# SCH.net
KiCad netlist of a schematic drawn in Altium Designer
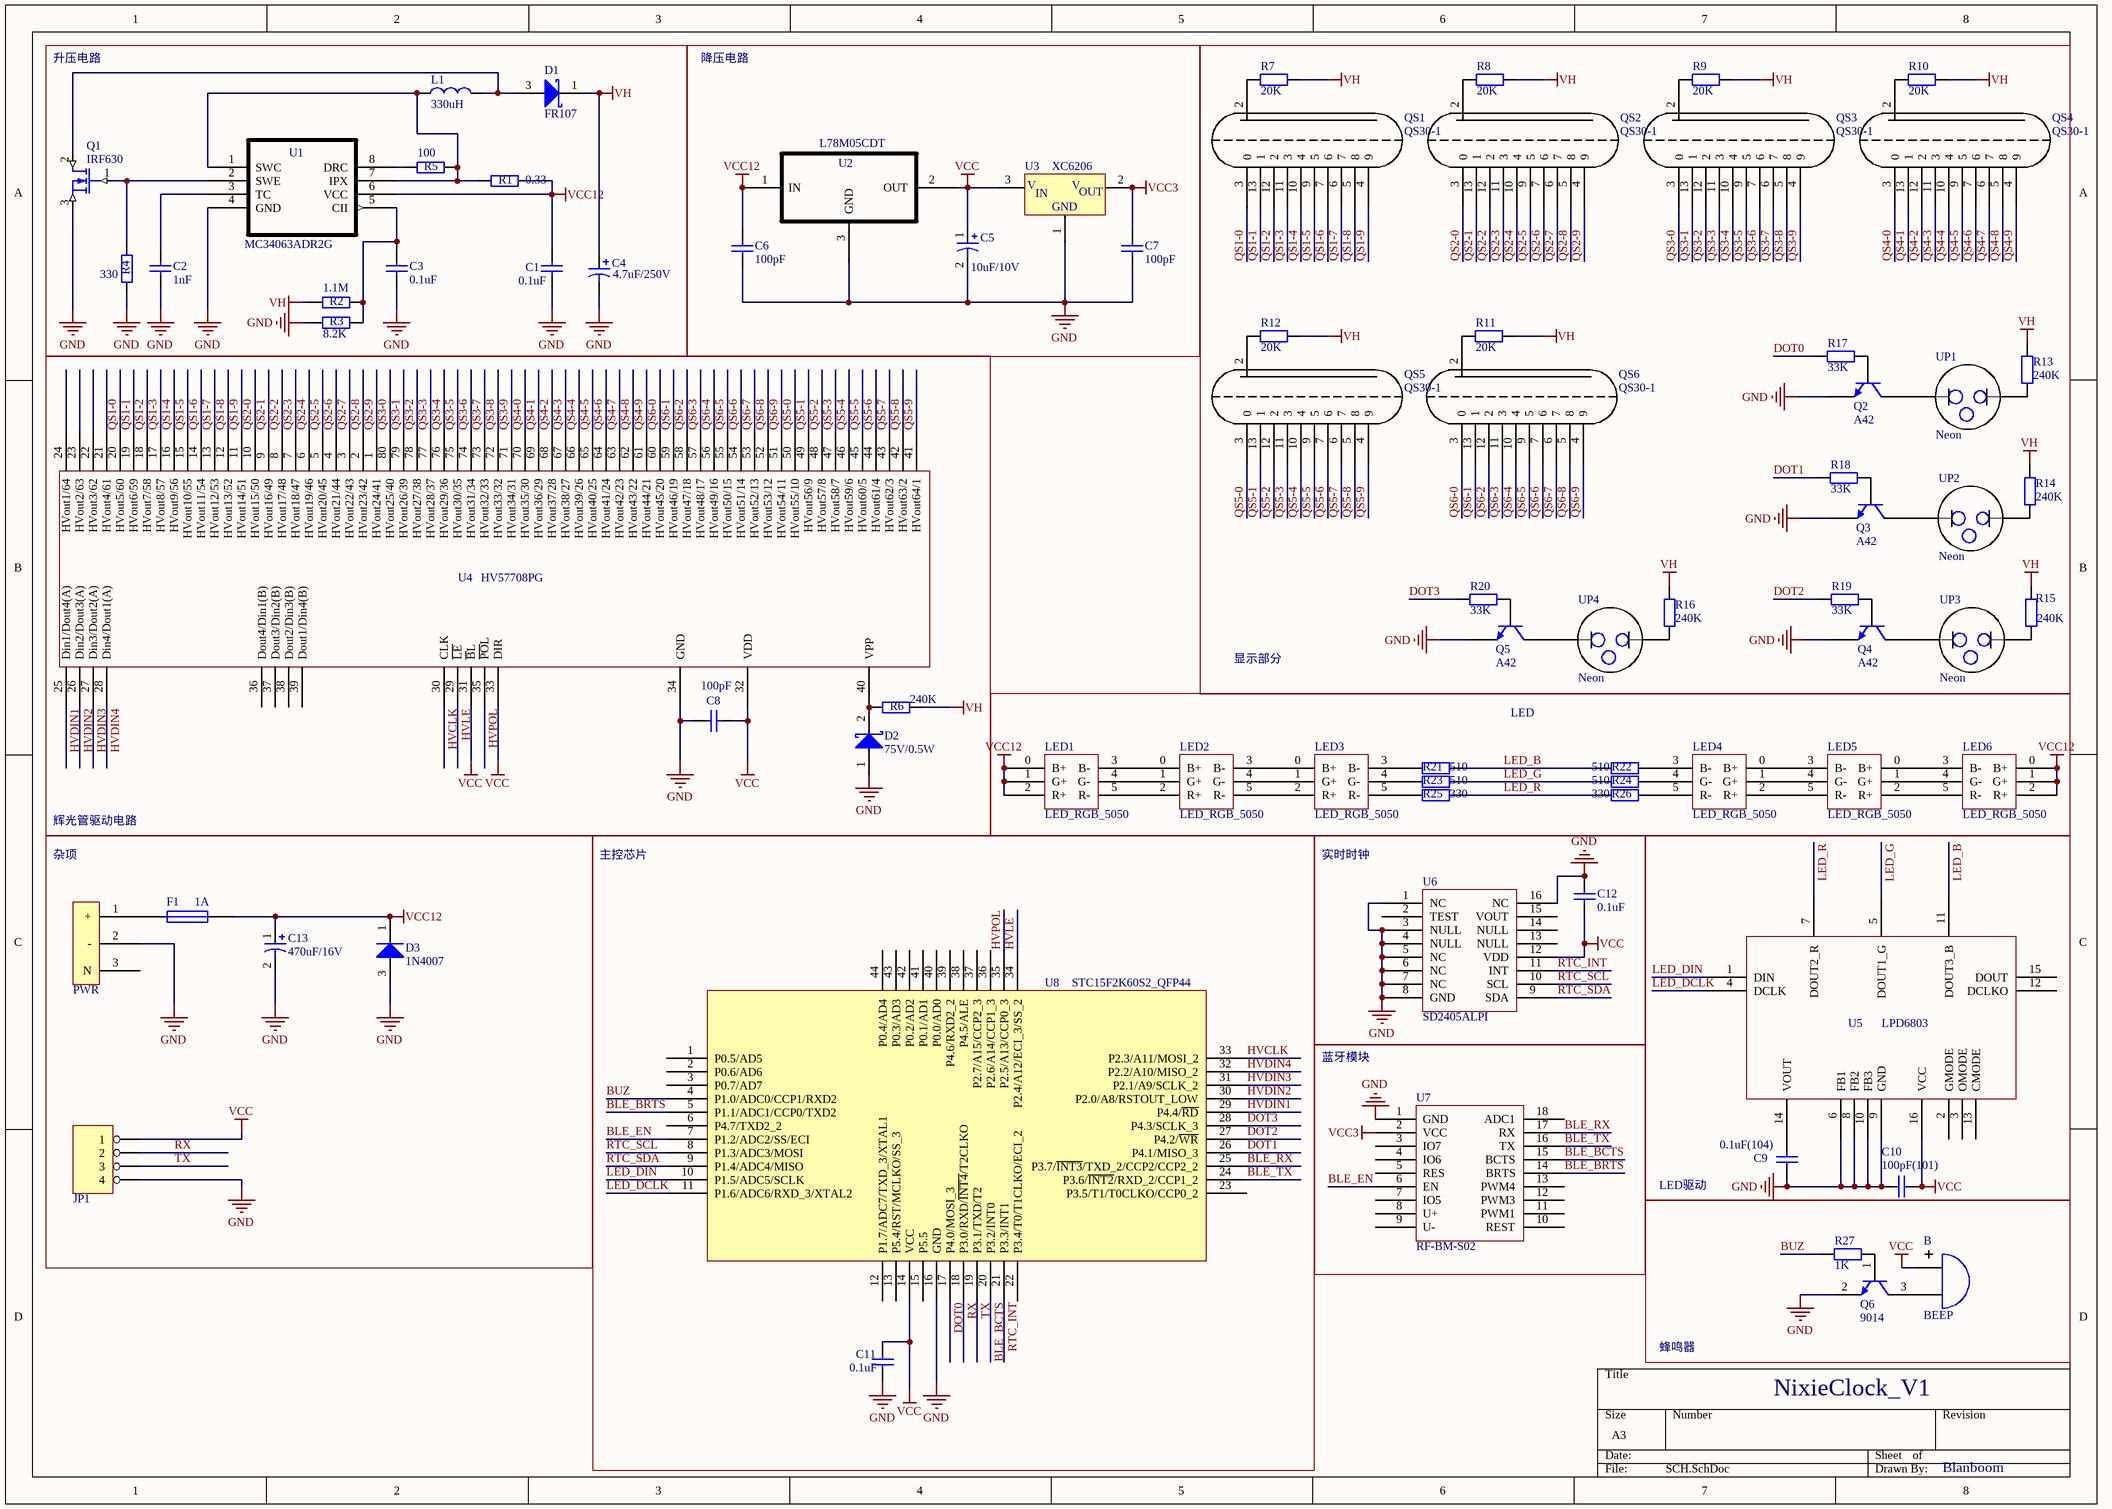
[diagram p0: SCH.SchDoc]

(export (version "E")
  (design (tool "Eeschema 10.0.6"))
  (components
    (comp (ref "B") (value "BEEP") (footprint "BEEP") (libsource (lib "MyLib") (part "BEEP")))
    (comp (ref "C1")
      (value "0.1uF")
      (footprint "0805")
      (description "Capacitor")
      (fields (field (name "Comment") "Cap") (field (name "PUBLISHER") "Altium Limited"))
      (libsource (lib "Miscellaneous Devices") (part "Cap"))
    )
    (comp (ref "C2")
      (value "1nF")
      (footprint "0805")
      (description "Capacitor")
      (fields (field (name "Comment") "Cap") (field (name "PUBLISHER") "Altium Limited"))
      (libsource (lib "Miscellaneous Devices") (part "Cap"))
    )
    (comp (ref "C3")
      (value "0.1uF")
      (footprint "0805")
      (description "Capacitor")
      (fields (field (name "Comment") "Cap") (field (name "PUBLISHER") "Altium Limited"))
      (libsource (lib "Miscellaneous Devices") (part "Cap"))
    )
    (comp (ref "C4")
      (value "4.7uF/250V")
      (footprint "1812")
      (description "Polarized Capacitor (Surface Mount)")
      (fields (field (name "Comment") "Cap Pol3") (field (name "PUBLISHER") "Altium Limited"))
      (libsource (lib "Miscellaneous Devices") (part "Cap Pol3"))
    )
    (comp (ref "C5")
      (value "10uF/10V")
      (footprint "1206_Diode")
      (description "Polarized Capacitor (Radial)")
      (fields (field (name "Comment") "Cap Pol1") (field (name "PUBLISHER") "Altium Limited"))
      (libsource (lib "Miscellaneous Devices") (part "Cap Pol1"))
    )
    (comp (ref "C6")
      (value "100pF")
      (footprint "0805")
      (description "Capacitor")
      (fields (field (name "Comment") "Cap") (field (name "PUBLISHER") "Altium Limited"))
      (libsource (lib "Miscellaneous Devices") (part "Cap"))
    )
    (comp (ref "C7")
      (value "100pF")
      (footprint "0805")
      (description "Capacitor")
      (fields (field (name "Comment") "Cap") (field (name "PUBLISHER") "Altium Limited"))
      (libsource (lib "Miscellaneous Devices") (part "Cap"))
    )
    (comp (ref "C8")
      (value "100pF")
      (footprint "0805")
      (description "Capacitor")
      (fields (field (name "Comment") "Cap") (field (name "PUBLISHER") "Altium Limited"))
      (libsource (lib "Miscellaneous Devices") (part "Cap"))
    )
    (comp (ref "C9")
      (value "0.1uF(104)")
      (footprint "0805")
      (description "Capacitor")
      (fields (field (name "Comment") "Cap") (field (name "PUBLISHER") "Altium Limited"))
      (libsource (lib "Miscellaneous Devices") (part "Cap"))
    )
    (comp (ref "C10")
      (value "100pF(101)")
      (footprint "0805")
      (description "Capacitor")
      (fields (field (name "Comment") "Cap") (field (name "PUBLISHER") "Altium Limited"))
      (libsource (lib "Miscellaneous Devices") (part "Cap"))
    )
    (comp (ref "C11")
      (value "0.1uF")
      (footprint "0805")
      (description "Capacitor")
      (fields (field (name "Comment") "Cap") (field (name "PUBLISHER") "Altium Limited"))
      (libsource (lib "Miscellaneous Devices") (part "Cap"))
    )
    (comp (ref "C12")
      (value "0.1uF")
      (footprint "0805")
      (description "Capacitor")
      (fields (field (name "Comment") "Cap") (field (name "PUBLISHER") "Altium Limited"))
      (libsource (lib "Miscellaneous Devices") (part "Cap"))
    )
    (comp (ref "C13")
      (value "470uF/16V")
      (footprint "7343")
      (description "Polarized Capacitor (Radial)")
      (fields (field (name "Comment") "Cap Pol1") (field (name "PUBLISHER") "Altium Limited"))
      (libsource (lib "Miscellaneous Devices") (part "Cap Pol1"))
    )
    (comp (ref "D1")
      (value "FR107")
      (footprint "DO-214AC")
      (description "Schottky Rectifier")
      (fields (field (name "PUBLISHER") "Altium Limited"))
      (libsource (lib "Miscellaneous Devices") (part "Diode 18TQ045"))
    )
    (comp (ref "D2")
      (value "75V/0.5W")
      (footprint "1206_Diode")
      (description "Schottky Rectifier")
      (fields (field (name "PUBLISHER") "Altium Limited"))
      (libsource (lib "Miscellaneous Devices") (part "Diode 10TQ040"))
    )
    (comp (ref "D3")
      (value "1N4007")
      (footprint "DO-214AC")
      (description "Default Diode")
      (fields (field (name "PUBLISHER") "Altium Limited"))
      (libsource (lib "Miscellaneous Devices") (part "Diode"))
    )
    (comp (ref "F1")
      (value "1A")
      (footprint "1206")
      (description "Fuse")
      (fields (field (name "PUBLISHER") "Altium Limited"))
      (libsource (lib "Miscellaneous Devices") (part "Fuse 1"))
    )
    (comp (ref "JP1")
      (value "Header4")
      (footprint "HEADER4")
      (description "4 Pin Header")
      (libsource (lib "插件") (part "4 HEADER"))
    )
    (comp (ref "L1") (value "330uH") (footprint "330uH") (libsource (lib "SCH") (part "L")))
    (comp (ref "LED1")
      (value "LED_RGB_5050")
      (footprint "LED_RGB_5050")
      (libsource (lib "") (part "LED_RGB_5050_1"))
    )
    (comp (ref "LED2")
      (value "LED_RGB_5050")
      (footprint "LED_RGB_5050")
      (libsource (lib "") (part "LED_RGB_5050_1"))
    )
    (comp (ref "LED3")
      (value "LED_RGB_5050")
      (footprint "LED_RGB_5050")
      (libsource (lib "") (part "LED_RGB_5050_1"))
    )
    (comp (ref "LED4")
      (value "LED_RGB_5050")
      (footprint "LED_RGB_5050")
      (libsource (lib "SCH") (part "LED_RGB_5050"))
    )
    (comp (ref "LED5")
      (value "LED_RGB_5050")
      (footprint "LED_RGB_5050")
      (libsource (lib "SCH") (part "LED_RGB_5050"))
    )
    (comp (ref "LED6")
      (value "LED_RGB_5050")
      (footprint "LED_RGB_5050")
      (libsource (lib "SCH") (part "LED_RGB_5050"))
    )
    (comp (ref "PWR") (value "PWR") (footprint "DC-044") (libsource (lib "SCH") (part "header2")))
    (comp (ref "Q1")
      (value "IRF630")
      (footprint "TO-263")
      (description "N-Channel MOSFET")
      (libsource (lib "SCH") (part "IRF630"))
    )
    (comp (ref "Q2")
      (value "A42")
      (footprint "SOT-23-BJT")
      (description "NPN General Purpose Amplifier")
      (fields (field (name "PUBLISHER") "Altium Limited"))
      (libsource (lib "Miscellaneous Devices") (part "2N3904"))
    )
    (comp (ref "Q3")
      (value "A42")
      (footprint "SOT-23-BJT")
      (description "NPN General Purpose Amplifier")
      (fields (field (name "PUBLISHER") "Altium Limited"))
      (libsource (lib "Miscellaneous Devices") (part "2N3904"))
    )
    (comp (ref "Q4")
      (value "A42")
      (footprint "SOT-23-BJT")
      (description "NPN General Purpose Amplifier")
      (fields (field (name "PUBLISHER") "Altium Limited"))
      (libsource (lib "Miscellaneous Devices") (part "2N3904"))
    )
    (comp (ref "Q5")
      (value "A42")
      (footprint "SOT-23-BJT")
      (description "NPN General Purpose Amplifier")
      (fields (field (name "PUBLISHER") "Altium Limited"))
      (libsource (lib "Miscellaneous Devices") (part "2N3904"))
    )
    (comp (ref "Q6")
      (value "9014")
      (footprint "SOT-23-BJT")
      (description "NPN General Purpose Amplifier")
      (fields (field (name "PUBLISHER") "Altium Limited"))
      (libsource (lib "") (part "2N3904_1"))
    )
    (comp (ref "QS1") (value "QS30-1") (footprint "QS30-1") (libsource (lib "SCH") (part "QS30-1")))
    (comp (ref "QS2") (value "QS30-1") (footprint "QS30-1") (libsource (lib "SCH") (part "QS30-1")))
    (comp (ref "QS3") (value "QS30-1") (footprint "QS30-1") (libsource (lib "SCH") (part "QS30-1")))
    (comp (ref "QS4") (value "QS30-1") (footprint "QS30-1") (libsource (lib "SCH") (part "QS30-1")))
    (comp (ref "QS5") (value "QS30-1") (footprint "QS30-1") (libsource (lib "SCH") (part "QS30-1")))
    (comp (ref "QS6") (value "QS30-1") (footprint "QS30-1") (libsource (lib "SCH") (part "QS30-1")))
    (comp (ref "R1")
      (value "0.33")
      (footprint "0805")
      (description "Resistor")
      (fields (field (name "Comment") "Res2") (field (name "PUBLISHER") "Altium Limited"))
      (libsource (lib "Miscellaneous Devices") (part "Res2"))
    )
    (comp (ref "R2")
      (value "1.1M")
      (footprint "0805")
      (description "Resistor")
      (fields (field (name "Comment") "Res2") (field (name "PUBLISHER") "Altium Limited"))
      (libsource (lib "Miscellaneous Devices") (part "Res2"))
    )
    (comp (ref "R3")
      (value "8.2K")
      (footprint "0805")
      (description "Resistor")
      (fields (field (name "Comment") "Res2") (field (name "PUBLISHER") "Altium Limited"))
      (libsource (lib "Miscellaneous Devices") (part "Res2"))
    )
    (comp (ref "R4")
      (value "330")
      (footprint "0805")
      (description "Resistor")
      (fields (field (name "Comment") "Res2") (field (name "PUBLISHER") "Altium Limited"))
      (libsource (lib "") (part "Res2_2"))
    )
    (comp (ref "R5")
      (value "100")
      (footprint "0805")
      (description "Resistor")
      (fields (field (name "Comment") "Res2") (field (name "PUBLISHER") "Altium Limited"))
      (libsource (lib "") (part "Res2_3"))
    )
    (comp (ref "R6")
      (value "240K")
      (footprint "0805")
      (description "Resistor")
      (fields (field (name "Comment") "Res2") (field (name "PUBLISHER") "Altium Limited"))
      (libsource (lib "Miscellaneous Devices") (part "Res2"))
    )
    (comp (ref "R7")
      (value "20K")
      (footprint "0805")
      (description "Resistor")
      (fields (field (name "Comment") "Res2") (field (name "PUBLISHER") "Altium Limited"))
      (libsource (lib "Miscellaneous Devices") (part "Res2"))
    )
    (comp (ref "R8")
      (value "20K")
      (footprint "0805")
      (description "Resistor")
      (fields (field (name "Comment") "Res2") (field (name "PUBLISHER") "Altium Limited"))
      (libsource (lib "Miscellaneous Devices") (part "Res2"))
    )
    (comp (ref "R9")
      (value "20K")
      (footprint "0805")
      (description "Resistor")
      (fields (field (name "Comment") "Res2") (field (name "PUBLISHER") "Altium Limited"))
      (libsource (lib "Miscellaneous Devices") (part "Res2"))
    )
    (comp (ref "R10")
      (value "20K")
      (footprint "0805")
      (description "Resistor")
      (fields (field (name "Comment") "Res2") (field (name "PUBLISHER") "Altium Limited"))
      (libsource (lib "Miscellaneous Devices") (part "Res2"))
    )
    (comp (ref "R11")
      (value "20K")
      (footprint "0805")
      (description "Resistor")
      (fields (field (name "Comment") "Res2") (field (name "PUBLISHER") "Altium Limited"))
      (libsource (lib "Miscellaneous Devices") (part "Res2"))
    )
    (comp (ref "R12")
      (value "20K")
      (footprint "0805")
      (description "Resistor")
      (fields (field (name "Comment") "Res2") (field (name "PUBLISHER") "Altium Limited"))
      (libsource (lib "Miscellaneous Devices") (part "Res2"))
    )
    (comp (ref "R13")
      (value "240K")
      (footprint "0805")
      (description "Resistor")
      (fields (field (name "Comment") "Res2") (field (name "PUBLISHER") "Altium Limited"))
      (libsource (lib "") (part "Res2_1"))
    )
    (comp (ref "R14")
      (value "240K")
      (footprint "0805")
      (description "Resistor")
      (fields (field (name "Comment") "Res2") (field (name "PUBLISHER") "Altium Limited"))
      (libsource (lib "") (part "Res2_1"))
    )
    (comp (ref "R15")
      (value "240K")
      (footprint "0805")
      (description "Resistor")
      (fields (field (name "Comment") "Res2") (field (name "PUBLISHER") "Altium Limited"))
      (libsource (lib "") (part "Res2_1"))
    )
    (comp (ref "R16")
      (value "240K")
      (footprint "0805")
      (description "Resistor")
      (fields (field (name "Comment") "Res2") (field (name "PUBLISHER") "Altium Limited"))
      (libsource (lib "") (part "Res2_1"))
    )
    (comp (ref "R17")
      (value "33K")
      (footprint "0805")
      (description "Resistor")
      (fields (field (name "Comment") "Res2") (field (name "PUBLISHER") "Altium Limited"))
      (libsource (lib "Miscellaneous Devices") (part "Res2"))
    )
    (comp (ref "R18")
      (value "33K")
      (footprint "0805")
      (description "Resistor")
      (fields (field (name "Comment") "Res2") (field (name "PUBLISHER") "Altium Limited"))
      (libsource (lib "Miscellaneous Devices") (part "Res2"))
    )
    (comp (ref "R19")
      (value "33K")
      (footprint "0805")
      (description "Resistor")
      (fields (field (name "Comment") "Res2") (field (name "PUBLISHER") "Altium Limited"))
      (libsource (lib "Miscellaneous Devices") (part "Res2"))
    )
    (comp (ref "R20")
      (value "33K")
      (footprint "0805")
      (description "Resistor")
      (fields (field (name "Comment") "Res2") (field (name "PUBLISHER") "Altium Limited"))
      (libsource (lib "Miscellaneous Devices") (part "Res2"))
    )
    (comp (ref "R21")
      (value "510")
      (footprint "0805")
      (description "Resistor")
      (fields (field (name "Comment") "Res2") (field (name "PUBLISHER") "Altium Limited"))
      (libsource (lib "Miscellaneous Devices") (part "Res2"))
    )
    (comp (ref "R22")
      (value "510")
      (footprint "0805")
      (description "Resistor")
      (fields (field (name "Comment") "Res2") (field (name "PUBLISHER") "Altium Limited"))
      (libsource (lib "Miscellaneous Devices") (part "Res2"))
    )
    (comp (ref "R23")
      (value "510")
      (footprint "0805")
      (description "Resistor")
      (fields (field (name "Comment") "Res2") (field (name "PUBLISHER") "Altium Limited"))
      (libsource (lib "Miscellaneous Devices") (part "Res2"))
    )
    (comp (ref "R24")
      (value "510")
      (footprint "0805")
      (description "Resistor")
      (fields (field (name "Comment") "Res2") (field (name "PUBLISHER") "Altium Limited"))
      (libsource (lib "Miscellaneous Devices") (part "Res2"))
    )
    (comp (ref "R25")
      (value "330")
      (footprint "0805")
      (description "Resistor")
      (fields (field (name "Comment") "Res2") (field (name "PUBLISHER") "Altium Limited"))
      (libsource (lib "Miscellaneous Devices") (part "Res2"))
    )
    (comp (ref "R26")
      (value "330")
      (footprint "0805")
      (description "Resistor")
      (fields (field (name "Comment") "Res2") (field (name "PUBLISHER") "Altium Limited"))
      (libsource (lib "Miscellaneous Devices") (part "Res2"))
    )
    (comp (ref "R27")
      (value "1K")
      (footprint "0805")
      (description "Resistor")
      (fields (field (name "Comment") "Res2") (field (name "PUBLISHER") "Altium Limited"))
      (libsource (lib "Miscellaneous Devices") (part "Res2"))
    )
    (comp (ref "U1")
      (value "MC34063ADR2G")
      (footprint "SO-8-M")
      (description "Imported")
      (libsource (lib "SCH") (part "MC34063ACD-TR"))
    )
    (comp (ref "U2")
      (value "L78M05CDT")
      (footprint "DPAK-M")
      (description "Imported")
      (libsource (lib "SCH") (part "L78M05CDT"))
    )
    (comp (ref "U3")
      (value "XC6206")
      (footprint "SOT-23")
      (description "3-Terminal Positive Voltage Regulator")
      (libsource (lib "SCH") (part "XC6206"))
    )
    (comp (ref "U4") (value "HV57708PG") (footprint "PQFP80") (libsource (lib "SCH") (part "HV57708PG")))
    (comp (ref "U5") (value "LPD6803") (footprint "SO-16") (libsource (lib "SCH") (part "LPD6803")))
    (comp (ref "U6") (value "SD2405ALPI") (footprint "DIP16") (libsource (lib "SCH") (part "SD2405ALPI")))
    (comp (ref "U7") (value "RF-BM-S02") (footprint "RF-BM-S02") (libsource (lib "SCH") (part "RF-BM-S02")))
    (comp (ref "U8")
      (value "STC15F2K60S2_QFP44")
      (footprint "LQFP44")
      (libsource (lib "SCH") (part "STC15F2K60S2_QFP44"))
    )
    (comp (ref "UP1") (value "Neon") (footprint "Neon") (libsource (lib "SCH") (part "Neon")))
    (comp (ref "UP2") (value "Neon") (footprint "Neon") (libsource (lib "SCH") (part "Neon")))
    (comp (ref "UP3") (value "Neon") (footprint "Neon") (libsource (lib "SCH") (part "Neon")))
    (comp (ref "UP4") (value "Neon") (footprint "Neon") (libsource (lib "SCH") (part "Neon")))
  )
  (nets
    (net (code "1") (name "/BLE_BCTS") (class "Default")
      (node (ref "U7") (pin "15") (pinfunction "BCTS_15") (pintype "passive"))
      (node (ref "U8") (pin "20") (pinfunction "P3.2/INT0_20") (pintype "passive"))
    )
    (net (code "2") (name "/BLE_BRTS") (class "Default")
      (node (ref "U7") (pin "14") (pinfunction "BRTS_14") (pintype "passive"))
      (node (ref "U8") (pin "5") (pinfunction "P1.1/ADC1/CCP0/TXD2_5") (pintype "passive"))
    )
    (net (code "3") (name "/BLE_EN") (class "Default")
      (node (ref "U7") (pin "6") (pinfunction "EN_6") (pintype "passive"))
      (node (ref "U8") (pin "7") (pinfunction "P1.2/ADC2/SS/ECI_7") (pintype "passive"))
    )
    (net (code "4") (name "/BLE_RX") (class "Default")
      (node (ref "U7") (pin "17") (pinfunction "RX_17") (pintype "passive"))
      (node (ref "U8") (pin "25") (pinfunction "P3.7/~{INT3}/TXD_2/CCP2/CCP2_2_25") (pintype "passive"))
    )
    (net (code "5") (name "/BLE_TX") (class "Default")
      (node (ref "U7") (pin "16") (pinfunction "TX_16") (pintype "passive"))
      (node (ref "U8") (pin "24") (pinfunction "P3.6/~{INT2}/RXD_2/CCP1_2_24") (pintype "passive"))
    )
    (net (code "6") (name "/BUZ") (class "Default")
      (node (ref "R27") (pin "1") (pinfunction "1_1") (pintype "passive"))
      (node (ref "U8") (pin "4") (pinfunction "P1.0/ADC0/CCP1/RXD2_4") (pintype "passive"))
    )
    (net (code "7") (name "/DOT0") (class "Default")
      (node (ref "R17") (pin "1") (pinfunction "1_1") (pintype "passive"))
      (node (ref "U8") (pin "17") (pinfunction "P4.0/MOSI_3_17") (pintype "passive"))
    )
    (net (code "8") (name "/DOT1") (class "Default")
      (node (ref "R18") (pin "1") (pinfunction "1_1") (pintype "passive"))
      (node (ref "U8") (pin "26") (pinfunction "P4.1/MISO_3_26") (pintype "passive"))
    )
    (net (code "9") (name "/DOT2") (class "Default")
      (node (ref "R19") (pin "1") (pinfunction "1_1") (pintype "passive"))
      (node (ref "U8") (pin "27") (pinfunction "P4.2/~{WR}_27") (pintype "passive"))
    )
    (net (code "10") (name "/DOT3") (class "Default")
      (node (ref "R20") (pin "1") (pinfunction "1_1") (pintype "passive"))
      (node (ref "U8") (pin "28") (pinfunction "P4.3/SCLK_3_28") (pintype "passive"))
    )
    (net (code "11") (name "/HVCLK") (class "Default")
      (node (ref "U4") (pin "30") (pinfunction "CLK_30") (pintype "passive"))
      (node (ref "U8") (pin "33") (pinfunction "P2.3/A11/MOSI_2_33") (pintype "passive"))
    )
    (net (code "12") (name "/HVDIN1") (class "Default")
      (node (ref "U4") (pin "25") (pinfunction "Din1/Dout4(A)_25") (pintype "passive"))
      (node (ref "U8") (pin "29") (pinfunction "P4.4/~{RD}_29") (pintype "passive"))
    )
    (net (code "13") (name "/HVDIN2") (class "Default")
      (node (ref "U4") (pin "26") (pinfunction "Din2/Dout3(A)_26") (pintype "passive"))
      (node (ref "U8") (pin "30") (pinfunction "P2.0/A8/RSTOUT_LOW_30") (pintype "passive"))
    )
    (net (code "14") (name "/HVDIN3") (class "Default")
      (node (ref "U4") (pin "27") (pinfunction "Din3/Dout2(A)_27") (pintype "passive"))
      (node (ref "U8") (pin "31") (pinfunction "P2.1/A9/SCLK_2_31") (pintype "passive"))
    )
    (net (code "15") (name "/HVDIN4") (class "Default")
      (node (ref "U4") (pin "28") (pinfunction "Din4/Dout1(A)_28") (pintype "passive"))
      (node (ref "U8") (pin "32") (pinfunction "P2.2/A10/MISO_2_32") (pintype "passive"))
    )
    (net (code "16") (name "/HVLE") (class "Default")
      (node (ref "U4") (pin "29") (pinfunction "~{LE}_29") (pintype "passive"))
      (node (ref "U8") (pin "34") (pinfunction "P2.4/A12/ECI_3/SS_2_34") (pintype "passive"))
    )
    (net (code "17") (name "/HVPOL") (class "Default")
      (node (ref "U4") (pin "35") (pinfunction "~{PO}L_35") (pintype "passive"))
      (node (ref "U8") (pin "35") (pinfunction "P2.5/A13/CCP0_3_35") (pintype "passive"))
    )
    (net (code "18") (name "/LED_B") (class "Default")
      (node (ref "R21") (pin "2") (pinfunction "2_2") (pintype "passive"))
      (node (ref "R22") (pin "1") (pinfunction "1_1") (pintype "passive"))
      (node (ref "U5") (pin "11") (pinfunction "DOUT3_B_11") (pintype "passive"))
    )
    (net (code "19") (name "/LED_DCLK") (class "Default")
      (node (ref "U5") (pin "4") (pinfunction "DCLK_4") (pintype "passive"))
      (node (ref "U8") (pin "11") (pinfunction "P1.6/ADC6/RXD_3/XTAL2_11") (pintype "passive"))
    )
    (net (code "20") (name "/LED_DIN") (class "Default")
      (node (ref "U5") (pin "1") (pinfunction "DIN_1") (pintype "passive"))
      (node (ref "U8") (pin "10") (pinfunction "P1.5/ADC5/SCLK_10") (pintype "passive"))
    )
    (net (code "21") (name "/LED_G") (class "Default")
      (node (ref "R23") (pin "2") (pinfunction "2_2") (pintype "passive"))
      (node (ref "R24") (pin "1") (pinfunction "1_1") (pintype "passive"))
      (node (ref "U5") (pin "5") (pinfunction "DOUT1_G_5") (pintype "passive"))
    )
    (net (code "22") (name "/LED_R") (class "Default")
      (node (ref "R25") (pin "2") (pinfunction "2_2") (pintype "passive"))
      (node (ref "R26") (pin "1") (pinfunction "1_1") (pintype "passive"))
      (node (ref "U5") (pin "7") (pinfunction "DOUT2_R_7") (pintype "passive"))
    )
    (net (code "23") (name "/QS1-0") (class "Default")
      (node (ref "QS1") (pin "3") (pinfunction "0_3") (pintype "passive"))
      (node (ref "U4") (pin "20") (pinfunction "HVout5/60_20") (pintype "passive"))
    )
    (net (code "24") (name "/QS1-1") (class "Default")
      (node (ref "QS1") (pin "13") (pinfunction "1_13") (pintype "passive"))
      (node (ref "U4") (pin "19") (pinfunction "HVout6/59_19") (pintype "passive"))
    )
    (net (code "25") (name "/QS1-2") (class "Default")
      (node (ref "QS1") (pin "12") (pinfunction "2_12") (pintype "passive"))
      (node (ref "U4") (pin "18") (pinfunction "HVout7/58_18") (pintype "passive"))
    )
    (net (code "26") (name "/QS1-3") (class "Default")
      (node (ref "QS1") (pin "11") (pinfunction "3_11") (pintype "passive"))
      (node (ref "U4") (pin "17") (pinfunction "HVout8/57_17") (pintype "passive"))
    )
    (net (code "27") (name "/QS1-4") (class "Default")
      (node (ref "QS1") (pin "10") (pinfunction "4_10") (pintype "passive"))
      (node (ref "U4") (pin "16") (pinfunction "HVout9/56_16") (pintype "passive"))
    )
    (net (code "28") (name "/QS1-5") (class "Default")
      (node (ref "QS1") (pin "9") (pinfunction "5_9") (pintype "passive"))
      (node (ref "U4") (pin "15") (pinfunction "HVout10/55_15") (pintype "passive"))
    )
    (net (code "29") (name "/QS1-6") (class "Default")
      (node (ref "QS1") (pin "7") (pinfunction "6_7") (pintype "passive"))
      (node (ref "U4") (pin "14") (pinfunction "HVout11/54_14") (pintype "passive"))
    )
    (net (code "30") (name "/QS1-7") (class "Default")
      (node (ref "QS1") (pin "6") (pinfunction "7_6") (pintype "passive"))
      (node (ref "U4") (pin "13") (pinfunction "HVout12/53_13") (pintype "passive"))
    )
    (net (code "31") (name "/QS1-8") (class "Default")
      (node (ref "QS1") (pin "5") (pinfunction "8_5") (pintype "passive"))
      (node (ref "U4") (pin "12") (pinfunction "HVout13/52_12") (pintype "passive"))
    )
    (net (code "32") (name "/QS1-9") (class "Default")
      (node (ref "QS1") (pin "4") (pinfunction "9_4") (pintype "passive"))
      (node (ref "U4") (pin "11") (pinfunction "HVout14/51_11") (pintype "passive"))
    )
    (net (code "33") (name "/QS2-0") (class "Default")
      (node (ref "QS2") (pin "3") (pinfunction "0_3") (pintype "passive"))
      (node (ref "U4") (pin "10") (pinfunction "HVout15/50_10") (pintype "passive"))
    )
    (net (code "34") (name "/QS2-1") (class "Default")
      (node (ref "QS2") (pin "13") (pinfunction "1_13") (pintype "passive"))
      (node (ref "U4") (pin "9") (pinfunction "HVout16/49_9") (pintype "passive"))
    )
    (net (code "35") (name "/QS2-2") (class "Default")
      (node (ref "QS2") (pin "12") (pinfunction "2_12") (pintype "passive"))
      (node (ref "U4") (pin "8") (pinfunction "HVout17/48_8") (pintype "passive"))
    )
    (net (code "36") (name "/QS2-3") (class "Default")
      (node (ref "QS2") (pin "11") (pinfunction "3_11") (pintype "passive"))
      (node (ref "U4") (pin "7") (pinfunction "HVout18/47_7") (pintype "passive"))
    )
    (net (code "37") (name "/QS2-4") (class "Default")
      (node (ref "QS2") (pin "10") (pinfunction "4_10") (pintype "passive"))
      (node (ref "U4") (pin "6") (pinfunction "HVout19/46_6") (pintype "passive"))
    )
    (net (code "38") (name "/QS2-5") (class "Default")
      (node (ref "QS2") (pin "9") (pinfunction "5_9") (pintype "passive"))
      (node (ref "U4") (pin "5") (pinfunction "HVout20/45_5") (pintype "passive"))
    )
    (net (code "39") (name "/QS2-6") (class "Default")
      (node (ref "QS2") (pin "7") (pinfunction "6_7") (pintype "passive"))
      (node (ref "U4") (pin "4") (pinfunction "HVout21/44_4") (pintype "passive"))
    )
    (net (code "40") (name "/QS2-7") (class "Default")
      (node (ref "QS2") (pin "6") (pinfunction "7_6") (pintype "passive"))
      (node (ref "U4") (pin "3") (pinfunction "HVout22/43_3") (pintype "passive"))
    )
    (net (code "41") (name "/QS2-8") (class "Default")
      (node (ref "QS2") (pin "5") (pinfunction "8_5") (pintype "passive"))
      (node (ref "U4") (pin "2") (pinfunction "HVout23/42_2") (pintype "passive"))
    )
    (net (code "42") (name "/QS2-9") (class "Default")
      (node (ref "QS2") (pin "4") (pinfunction "9_4") (pintype "passive"))
      (node (ref "U4") (pin "1") (pinfunction "HVout24/41_1") (pintype "passive"))
    )
    (net (code "43") (name "/QS3-0") (class "Default")
      (node (ref "QS3") (pin "3") (pinfunction "0_3") (pintype "passive"))
      (node (ref "U4") (pin "80") (pinfunction "HVout25/40_80") (pintype "passive"))
    )
    (net (code "44") (name "/QS3-1") (class "Default")
      (node (ref "QS3") (pin "13") (pinfunction "1_13") (pintype "passive"))
      (node (ref "U4") (pin "79") (pinfunction "HVout26/39_79") (pintype "passive"))
    )
    (net (code "45") (name "/QS3-2") (class "Default")
      (node (ref "QS3") (pin "12") (pinfunction "2_12") (pintype "passive"))
      (node (ref "U4") (pin "78") (pinfunction "HVout27/38_78") (pintype "passive"))
    )
    (net (code "46") (name "/QS3-3") (class "Default")
      (node (ref "QS3") (pin "11") (pinfunction "3_11") (pintype "passive"))
      (node (ref "U4") (pin "77") (pinfunction "HVout28/37_77") (pintype "passive"))
    )
    (net (code "47") (name "/QS3-4") (class "Default")
      (node (ref "QS3") (pin "10") (pinfunction "4_10") (pintype "passive"))
      (node (ref "U4") (pin "76") (pinfunction "HVout29/36_76") (pintype "passive"))
    )
    (net (code "48") (name "/QS3-5") (class "Default")
      (node (ref "QS3") (pin "9") (pinfunction "5_9") (pintype "passive"))
      (node (ref "U4") (pin "75") (pinfunction "HVout30/35_75") (pintype "passive"))
    )
    (net (code "49") (name "/QS3-6") (class "Default")
      (node (ref "QS3") (pin "7") (pinfunction "6_7") (pintype "passive"))
      (node (ref "U4") (pin "74") (pinfunction "HVout31/34_74") (pintype "passive"))
    )
    (net (code "50") (name "/QS3-7") (class "Default")
      (node (ref "QS3") (pin "6") (pinfunction "7_6") (pintype "passive"))
      (node (ref "U4") (pin "73") (pinfunction "HVout32/33_73") (pintype "passive"))
    )
    (net (code "51") (name "/QS3-8") (class "Default")
      (node (ref "QS3") (pin "5") (pinfunction "8_5") (pintype "passive"))
      (node (ref "U4") (pin "72") (pinfunction "HVout33/32_72") (pintype "passive"))
    )
    (net (code "52") (name "/QS3-9") (class "Default")
      (node (ref "QS3") (pin "4") (pinfunction "9_4") (pintype "passive"))
      (node (ref "U4") (pin "71") (pinfunction "HVout34/31_71") (pintype "passive"))
    )
    (net (code "53") (name "/QS4-0") (class "Default")
      (node (ref "QS4") (pin "3") (pinfunction "0_3") (pintype "passive"))
      (node (ref "U4") (pin "70") (pinfunction "HVout35/30_70") (pintype "passive"))
    )
    (net (code "54") (name "/QS4-1") (class "Default")
      (node (ref "QS4") (pin "13") (pinfunction "1_13") (pintype "passive"))
      (node (ref "U4") (pin "69") (pinfunction "HVout36/29_69") (pintype "passive"))
    )
    (net (code "55") (name "/QS4-2") (class "Default")
      (node (ref "QS4") (pin "12") (pinfunction "2_12") (pintype "passive"))
      (node (ref "U4") (pin "68") (pinfunction "HVout37/28_68") (pintype "passive"))
    )
    (net (code "56") (name "/QS4-3") (class "Default")
      (node (ref "QS4") (pin "11") (pinfunction "3_11") (pintype "passive"))
      (node (ref "U4") (pin "67") (pinfunction "HVout38/27_67") (pintype "passive"))
    )
    (net (code "57") (name "/QS4-4") (class "Default")
      (node (ref "QS4") (pin "10") (pinfunction "4_10") (pintype "passive"))
      (node (ref "U4") (pin "66") (pinfunction "HVout39/26_66") (pintype "passive"))
    )
    (net (code "58") (name "/QS4-5") (class "Default")
      (node (ref "QS4") (pin "9") (pinfunction "5_9") (pintype "passive"))
      (node (ref "U4") (pin "65") (pinfunction "HVout40/25_65") (pintype "passive"))
    )
    (net (code "59") (name "/QS4-6") (class "Default")
      (node (ref "QS4") (pin "7") (pinfunction "6_7") (pintype "passive"))
      (node (ref "U4") (pin "64") (pinfunction "HVout41/24_64") (pintype "passive"))
    )
    (net (code "60") (name "/QS4-7") (class "Default")
      (node (ref "QS4") (pin "6") (pinfunction "7_6") (pintype "passive"))
      (node (ref "U4") (pin "63") (pinfunction "HVout42/23_63") (pintype "passive"))
    )
    (net (code "61") (name "/QS4-8") (class "Default")
      (node (ref "QS4") (pin "5") (pinfunction "8_5") (pintype "passive"))
      (node (ref "U4") (pin "62") (pinfunction "HVout43/22_62") (pintype "passive"))
    )
    (net (code "62") (name "/QS4-9") (class "Default")
      (node (ref "QS4") (pin "4") (pinfunction "9_4") (pintype "passive"))
      (node (ref "U4") (pin "61") (pinfunction "HVout44/21_61") (pintype "passive"))
    )
    (net (code "63") (name "/QS5-0") (class "Default")
      (node (ref "QS5") (pin "3") (pinfunction "0_3") (pintype "passive"))
      (node (ref "U4") (pin "50") (pinfunction "HVout55/10_50") (pintype "passive"))
    )
    (net (code "64") (name "/QS5-1") (class "Default")
      (node (ref "QS5") (pin "13") (pinfunction "1_13") (pintype "passive"))
      (node (ref "U4") (pin "49") (pinfunction "HVout56/9_49") (pintype "passive"))
    )
    (net (code "65") (name "/QS5-2") (class "Default")
      (node (ref "QS5") (pin "12") (pinfunction "2_12") (pintype "passive"))
      (node (ref "U4") (pin "48") (pinfunction "HVout57/8_48") (pintype "passive"))
    )
    (net (code "66") (name "/QS5-3") (class "Default")
      (node (ref "QS5") (pin "11") (pinfunction "3_11") (pintype "passive"))
      (node (ref "U4") (pin "47") (pinfunction "HVout58/7_47") (pintype "passive"))
    )
    (net (code "67") (name "/QS5-4") (class "Default")
      (node (ref "QS5") (pin "10") (pinfunction "4_10") (pintype "passive"))
      (node (ref "U4") (pin "46") (pinfunction "HVout59/6_46") (pintype "passive"))
    )
    (net (code "68") (name "/QS5-5") (class "Default")
      (node (ref "QS5") (pin "9") (pinfunction "5_9") (pintype "passive"))
      (node (ref "U4") (pin "45") (pinfunction "HVout60/5_45") (pintype "passive"))
    )
    (net (code "69") (name "/QS5-6") (class "Default")
      (node (ref "QS5") (pin "7") (pinfunction "6_7") (pintype "passive"))
      (node (ref "U4") (pin "44") (pinfunction "HVout61/4_44") (pintype "passive"))
    )
    (net (code "70") (name "/QS5-7") (class "Default")
      (node (ref "QS5") (pin "6") (pinfunction "7_6") (pintype "passive"))
      (node (ref "U4") (pin "43") (pinfunction "HVout62/3_43") (pintype "passive"))
    )
    (net (code "71") (name "/QS5-8") (class "Default")
      (node (ref "QS5") (pin "5") (pinfunction "8_5") (pintype "passive"))
      (node (ref "U4") (pin "42") (pinfunction "HVout63/2_42") (pintype "passive"))
    )
    (net (code "72") (name "/QS5-9") (class "Default")
      (node (ref "QS5") (pin "4") (pinfunction "9_4") (pintype "passive"))
      (node (ref "U4") (pin "41") (pinfunction "HVout64/1_41") (pintype "passive"))
    )
    (net (code "73") (name "/QS6-0") (class "Default")
      (node (ref "QS6") (pin "3") (pinfunction "0_3") (pintype "passive"))
      (node (ref "U4") (pin "60") (pinfunction "HVout45/20_60") (pintype "passive"))
    )
    (net (code "74") (name "/QS6-1") (class "Default")
      (node (ref "QS6") (pin "13") (pinfunction "1_13") (pintype "passive"))
      (node (ref "U4") (pin "59") (pinfunction "HVout46/19_59") (pintype "passive"))
    )
    (net (code "75") (name "/QS6-2") (class "Default")
      (node (ref "QS6") (pin "12") (pinfunction "2_12") (pintype "passive"))
      (node (ref "U4") (pin "58") (pinfunction "HVout47/18_58") (pintype "passive"))
    )
    (net (code "76") (name "/QS6-3") (class "Default")
      (node (ref "QS6") (pin "11") (pinfunction "3_11") (pintype "passive"))
      (node (ref "U4") (pin "57") (pinfunction "HVout48/17_57") (pintype "passive"))
    )
    (net (code "77") (name "/QS6-4") (class "Default")
      (node (ref "QS6") (pin "10") (pinfunction "4_10") (pintype "passive"))
      (node (ref "U4") (pin "56") (pinfunction "HVout49/16_56") (pintype "passive"))
    )
    (net (code "78") (name "/QS6-5") (class "Default")
      (node (ref "QS6") (pin "9") (pinfunction "5_9") (pintype "passive"))
      (node (ref "U4") (pin "55") (pinfunction "HVout50/15_55") (pintype "passive"))
    )
    (net (code "79") (name "/QS6-6") (class "Default")
      (node (ref "QS6") (pin "7") (pinfunction "6_7") (pintype "passive"))
      (node (ref "U4") (pin "54") (pinfunction "HVout51/14_54") (pintype "passive"))
    )
    (net (code "80") (name "/QS6-7") (class "Default")
      (node (ref "QS6") (pin "6") (pinfunction "7_6") (pintype "passive"))
      (node (ref "U4") (pin "53") (pinfunction "HVout52/13_53") (pintype "passive"))
    )
    (net (code "81") (name "/QS6-8") (class "Default")
      (node (ref "QS6") (pin "5") (pinfunction "8_5") (pintype "passive"))
      (node (ref "U4") (pin "52") (pinfunction "HVout53/12_52") (pintype "passive"))
    )
    (net (code "82") (name "/QS6-9") (class "Default")
      (node (ref "QS6") (pin "4") (pinfunction "9_4") (pintype "passive"))
      (node (ref "U4") (pin "51") (pinfunction "HVout54/11_51") (pintype "passive"))
    )
    (net (code "83") (name "/RTC_INT") (class "Default")
      (node (ref "U6") (pin "11") (pinfunction "INT_11") (pintype "passive"))
      (node (ref "U8") (pin "21") (pinfunction "P3.3/INT1_21") (pintype "passive"))
    )
    (net (code "84") (name "/RTC_SCL") (class "Default")
      (node (ref "U6") (pin "10") (pinfunction "SCL_10") (pintype "passive"))
      (node (ref "U8") (pin "8") (pinfunction "P1.3/ADC3/MOSI_8") (pintype "passive"))
    )
    (net (code "85") (name "/RTC_SDA") (class "Default")
      (node (ref "U6") (pin "9") (pinfunction "SDA_9") (pintype "passive"))
      (node (ref "U8") (pin "9") (pinfunction "P1.4/ADC4/MISO_9") (pintype "passive"))
    )
    (net (code "86") (name "/RX") (class "Default")
      (node (ref "JP1") (pin "2") (pinfunction "2_2") (pintype "passive"))
      (node (ref "U8") (pin "18") (pinfunction "P3.0/RXD/~{INT4}/T2CLKO_18") (pintype "passive"))
    )
    (net (code "87") (name "/TX") (class "Default")
      (node (ref "JP1") (pin "3") (pinfunction "3_3") (pintype "passive"))
      (node (ref "U8") (pin "19") (pinfunction "P3.1/TXD/T2_19") (pintype "passive"))
    )
    (net (code "88") (name "GND") (class "Default")
      (node (ref "C1") (pin "1") (pinfunction "1_1") (pintype "passive"))
      (node (ref "C10") (pin "1") (pinfunction "1_1") (pintype "passive"))
      (node (ref "C11") (pin "2") (pinfunction "2_2") (pintype "passive"))
      (node (ref "C12") (pin "2") (pinfunction "2_2") (pintype "passive"))
      (node (ref "C13") (pin "2") (pinfunction "2_2") (pintype "passive"))
      (node (ref "C2") (pin "1") (pinfunction "1_1") (pintype "passive"))
      (node (ref "C3") (pin "1") (pinfunction "1_1") (pintype "passive"))
      (node (ref "C4") (pin "2") (pinfunction "2_2") (pintype "passive"))
      (node (ref "C5") (pin "2") (pinfunction "2_2") (pintype "passive"))
      (node (ref "C6") (pin "1") (pinfunction "1_1") (pintype "passive"))
      (node (ref "C7") (pin "1") (pinfunction "1_1") (pintype "passive"))
      (node (ref "C8") (pin "1") (pinfunction "1_1") (pintype "passive"))
      (node (ref "C9") (pin "1") (pinfunction "1_1") (pintype "passive"))
      (node (ref "D2") (pin "1") (pinfunction "A_1") (pintype "passive"))
      (node (ref "D3") (pin "3") (pinfunction "A_3") (pintype "passive"))
      (node (ref "JP1") (pin "4") (pinfunction "4_4") (pintype "passive"))
      (node (ref "PWR") (pin "2") (pinfunction "-_2") (pintype "passive"))
      (node (ref "Q1") (pin "3") (pinfunction "S_3") (pintype "input"))
      (node (ref "Q2") (pin "2") (pinfunction "E_2") (pintype "passive"))
      (node (ref "Q3") (pin "2") (pinfunction "E_2") (pintype "passive"))
      (node (ref "Q4") (pin "2") (pinfunction "E_2") (pintype "passive"))
      (node (ref "Q5") (pin "2") (pinfunction "E_2") (pintype "passive"))
      (node (ref "Q6") (pin "2") (pinfunction "E_2") (pintype "passive"))
      (node (ref "R3") (pin "1") (pinfunction "1_1") (pintype "passive"))
      (node (ref "R4") (pin "1") (pinfunction "1_1") (pintype "passive"))
      (node (ref "U1") (pin "4") (pinfunction "GND_4") (pintype "power_in"))
      (node (ref "U2") (pin "3") (pinfunction "GND_3") (pintype "power_in"))
      (node (ref "U3") (pin "1") (pinfunction "GND_1") (pintype "passive"))
      (node (ref "U4") (pin "34") (pinfunction "GND_34") (pintype "passive"))
      (node (ref "U5") (pin "10") (pinfunction "FB3_10") (pintype "passive"))
      (node (ref "U5") (pin "6") (pinfunction "FB1_6") (pintype "passive"))
      (node (ref "U5") (pin "8") (pinfunction "FB2_8") (pintype "passive"))
      (node (ref "U5") (pin "9") (pinfunction "GND_9") (pintype "passive"))
      (node (ref "U6") (pin "1") (pinfunction "NC_1") (pintype "passive"))
      (node (ref "U6") (pin "16") (pinfunction "NC_16") (pintype "passive"))
      (node (ref "U6") (pin "3") (pinfunction "NULL_3") (pintype "passive"))
      (node (ref "U6") (pin "4") (pinfunction "NULL_4") (pintype "passive"))
      (node (ref "U6") (pin "5") (pinfunction "NC_5") (pintype "passive"))
      (node (ref "U6") (pin "6") (pinfunction "NC_6") (pintype "passive"))
      (node (ref "U6") (pin "7") (pinfunction "NC_7") (pintype "passive"))
      (node (ref "U6") (pin "8") (pinfunction "GND_8") (pintype "passive"))
      (node (ref "U7") (pin "1") (pinfunction "GND_1") (pintype "passive"))
      (node (ref "U8") (pin "16") (pinfunction "GND_16") (pintype "passive"))
    )
    (net (code "89") (name "Net-(B-B)") (class "Default")
      (node (ref "B") (pin "2") (pinfunction "B_2") (pintype "passive"))
      (node (ref "Q6") (pin "3") (pinfunction "C_3") (pintype "passive"))
    )
    (net (code "90") (name "Net-(D1-A)") (class "Default")
      (node (ref "D1") (pin "3") (pinfunction "A_3") (pintype "passive"))
      (node (ref "L1") (pin "1") (pintype "passive"))
      (node (ref "Q1") (pin "2") (pinfunction "D_2") (pintype "input"))
    )
    (net (code "91") (name "Net-(D2-K)") (class "Default")
      (node (ref "D2") (pin "2") (pinfunction "K_2") (pintype "passive"))
      (node (ref "R6") (pin "1") (pinfunction "1_1") (pintype "passive"))
      (node (ref "U4") (pin "40") (pinfunction "VPP_40") (pintype "passive"))
    )
    (net (code "92") (name "Net-(LED1-B-)") (class "Default")
      (node (ref "LED1") (pin "3") (pinfunction "B-_3") (pintype "passive"))
      (node (ref "LED2") (pin "0") (pinfunction "B+_0") (pintype "passive"))
    )
    (net (code "93") (name "Net-(LED1-G-)") (class "Default")
      (node (ref "LED1") (pin "4") (pinfunction "G-_4") (pintype "passive"))
      (node (ref "LED2") (pin "1") (pinfunction "G+_1") (pintype "passive"))
    )
    (net (code "94") (name "Net-(LED1-R-)") (class "Default")
      (node (ref "LED1") (pin "5") (pinfunction "R-_5") (pintype "passive"))
      (node (ref "LED2") (pin "2") (pinfunction "R+_2") (pintype "passive"))
    )
    (net (code "95") (name "Net-(LED2-B-)") (class "Default")
      (node (ref "LED2") (pin "3") (pinfunction "B-_3") (pintype "passive"))
      (node (ref "LED3") (pin "0") (pinfunction "B+_0") (pintype "passive"))
    )
    (net (code "96") (name "Net-(LED2-G-)") (class "Default")
      (node (ref "LED2") (pin "4") (pinfunction "G-_4") (pintype "passive"))
      (node (ref "LED3") (pin "1") (pinfunction "G+_1") (pintype "passive"))
    )
    (net (code "97") (name "Net-(LED2-R-)") (class "Default")
      (node (ref "LED2") (pin "5") (pinfunction "R-_5") (pintype "passive"))
      (node (ref "LED3") (pin "2") (pinfunction "R+_2") (pintype "passive"))
    )
    (net (code "98") (name "Net-(LED3-B-)") (class "Default")
      (node (ref "LED3") (pin "3") (pinfunction "B-_3") (pintype "passive"))
      (node (ref "R21") (pin "1") (pinfunction "1_1") (pintype "passive"))
    )
    (net (code "99") (name "Net-(LED3-G-)") (class "Default")
      (node (ref "LED3") (pin "4") (pinfunction "G-_4") (pintype "passive"))
      (node (ref "R23") (pin "1") (pinfunction "1_1") (pintype "passive"))
    )
    (net (code "100") (name "Net-(LED3-R-)") (class "Default")
      (node (ref "LED3") (pin "5") (pinfunction "R-_5") (pintype "passive"))
      (node (ref "R25") (pin "1") (pinfunction "1_1") (pintype "passive"))
    )
    (net (code "101") (name "Net-(LED4-B+)") (class "Default")
      (node (ref "LED4") (pin "0") (pinfunction "B+_0") (pintype "passive"))
      (node (ref "LED5") (pin "3") (pinfunction "B-_3") (pintype "passive"))
    )
    (net (code "102") (name "Net-(LED4-B-)") (class "Default")
      (node (ref "LED4") (pin "3") (pinfunction "B-_3") (pintype "passive"))
      (node (ref "R22") (pin "2") (pinfunction "2_2") (pintype "passive"))
    )
    (net (code "103") (name "Net-(LED4-G+)") (class "Default")
      (node (ref "LED4") (pin "1") (pinfunction "G+_1") (pintype "passive"))
      (node (ref "LED5") (pin "4") (pinfunction "G-_4") (pintype "passive"))
    )
    (net (code "104") (name "Net-(LED4-G-)") (class "Default")
      (node (ref "LED4") (pin "4") (pinfunction "G-_4") (pintype "passive"))
      (node (ref "R24") (pin "2") (pinfunction "2_2") (pintype "passive"))
    )
    (net (code "105") (name "Net-(LED4-R+)") (class "Default")
      (node (ref "LED4") (pin "2") (pinfunction "R+_2") (pintype "passive"))
      (node (ref "LED5") (pin "5") (pinfunction "R-_5") (pintype "passive"))
    )
    (net (code "106") (name "Net-(LED4-R-)") (class "Default")
      (node (ref "LED4") (pin "5") (pinfunction "R-_5") (pintype "passive"))
      (node (ref "R26") (pin "2") (pinfunction "2_2") (pintype "passive"))
    )
    (net (code "107") (name "Net-(LED5-B+)") (class "Default")
      (node (ref "LED5") (pin "0") (pinfunction "B+_0") (pintype "passive"))
      (node (ref "LED6") (pin "3") (pinfunction "B-_3") (pintype "passive"))
    )
    (net (code "108") (name "Net-(LED5-G+)") (class "Default")
      (node (ref "LED5") (pin "1") (pinfunction "G+_1") (pintype "passive"))
      (node (ref "LED6") (pin "4") (pinfunction "G-_4") (pintype "passive"))
    )
    (net (code "109") (name "Net-(LED5-R+)") (class "Default")
      (node (ref "LED5") (pin "2") (pinfunction "R+_2") (pintype "passive"))
      (node (ref "LED6") (pin "5") (pinfunction "R-_5") (pintype "passive"))
    )
    (net (code "110") (name "Net-(PWR-+)") (class "Default")
      (node (ref "F1") (pin "1") (pinfunction "1_1") (pintype "passive"))
      (node (ref "PWR") (pin "1") (pinfunction "+_1") (pintype "passive"))
    )
    (net (code "111") (name "Net-(Q1-G)") (class "Default")
      (node (ref "Q1") (pin "1") (pinfunction "G_1") (pintype "input"))
      (node (ref "R4") (pin "2") (pinfunction "2_2") (pintype "passive"))
      (node (ref "U1") (pin "2") (pinfunction "SWE_2") (pintype "passive"))
    )
    (net (code "112") (name "Net-(Q2-B)") (class "Default")
      (node (ref "Q2") (pin "1") (pinfunction "B_1") (pintype "passive"))
      (node (ref "R17") (pin "2") (pinfunction "2_2") (pintype "passive"))
    )
    (net (code "113") (name "Net-(Q2-C)") (class "Default")
      (node (ref "Q2") (pin "3") (pinfunction "C_3") (pintype "passive"))
      (node (ref "UP1") (pin "2") (pinfunction "2_2") (pintype "passive"))
    )
    (net (code "114") (name "Net-(Q3-B)") (class "Default")
      (node (ref "Q3") (pin "1") (pinfunction "B_1") (pintype "passive"))
      (node (ref "R18") (pin "2") (pinfunction "2_2") (pintype "passive"))
    )
    (net (code "115") (name "Net-(Q3-C)") (class "Default")
      (node (ref "Q3") (pin "3") (pinfunction "C_3") (pintype "passive"))
      (node (ref "UP2") (pin "2") (pinfunction "2_2") (pintype "passive"))
    )
    (net (code "116") (name "Net-(Q4-B)") (class "Default")
      (node (ref "Q4") (pin "1") (pinfunction "B_1") (pintype "passive"))
      (node (ref "R19") (pin "2") (pinfunction "2_2") (pintype "passive"))
    )
    (net (code "117") (name "Net-(Q4-C)") (class "Default")
      (node (ref "Q4") (pin "3") (pinfunction "C_3") (pintype "passive"))
      (node (ref "UP3") (pin "2") (pinfunction "2_2") (pintype "passive"))
    )
    (net (code "118") (name "Net-(Q5-B)") (class "Default")
      (node (ref "Q5") (pin "1") (pinfunction "B_1") (pintype "passive"))
      (node (ref "R20") (pin "2") (pinfunction "2_2") (pintype "passive"))
    )
    (net (code "119") (name "Net-(Q5-C)") (class "Default")
      (node (ref "Q5") (pin "3") (pinfunction "C_3") (pintype "passive"))
      (node (ref "UP4") (pin "2") (pinfunction "2_2") (pintype "passive"))
    )
    (net (code "120") (name "Net-(Q6-B)") (class "Default")
      (node (ref "Q6") (pin "1") (pinfunction "B_1") (pintype "passive"))
      (node (ref "R27") (pin "2") (pinfunction "2_2") (pintype "passive"))
    )
    (net (code "121") (name "Net-(QS1-10)") (class "Default")
      (node (ref "QS1") (pin "2") (pinfunction "10_2") (pintype "passive"))
      (node (ref "R7") (pin "1") (pinfunction "1_1") (pintype "passive"))
    )
    (net (code "122") (name "Net-(QS2-10)") (class "Default")
      (node (ref "QS2") (pin "2") (pinfunction "10_2") (pintype "passive"))
      (node (ref "R8") (pin "1") (pinfunction "1_1") (pintype "passive"))
    )
    (net (code "123") (name "Net-(QS3-10)") (class "Default")
      (node (ref "QS3") (pin "2") (pinfunction "10_2") (pintype "passive"))
      (node (ref "R9") (pin "1") (pinfunction "1_1") (pintype "passive"))
    )
    (net (code "124") (name "Net-(QS4-10)") (class "Default")
      (node (ref "QS4") (pin "2") (pinfunction "10_2") (pintype "passive"))
      (node (ref "R10") (pin "1") (pinfunction "1_1") (pintype "passive"))
    )
    (net (code "125") (name "Net-(QS5-10)") (class "Default")
      (node (ref "QS5") (pin "2") (pinfunction "10_2") (pintype "passive"))
      (node (ref "R12") (pin "1") (pinfunction "1_1") (pintype "passive"))
    )
    (net (code "126") (name "Net-(QS6-10)") (class "Default")
      (node (ref "QS6") (pin "2") (pinfunction "10_2") (pintype "passive"))
      (node (ref "R11") (pin "1") (pinfunction "1_1") (pintype "passive"))
    )
    (net (code "127") (name "Net-(R13-Pad2)") (class "Default")
      (node (ref "R13") (pin "2") (pinfunction "2_2") (pintype "passive"))
      (node (ref "UP1") (pin "1") (pinfunction "1_1") (pintype "passive"))
    )
    (net (code "128") (name "Net-(R14-Pad2)") (class "Default")
      (node (ref "R14") (pin "2") (pinfunction "2_2") (pintype "passive"))
      (node (ref "UP2") (pin "1") (pinfunction "1_1") (pintype "passive"))
    )
    (net (code "129") (name "Net-(R15-Pad2)") (class "Default")
      (node (ref "R15") (pin "2") (pinfunction "2_2") (pintype "passive"))
      (node (ref "UP3") (pin "1") (pinfunction "1_1") (pintype "passive"))
    )
    (net (code "130") (name "Net-(R16-Pad2)") (class "Default")
      (node (ref "R16") (pin "2") (pinfunction "2_2") (pintype "passive"))
      (node (ref "UP4") (pin "1") (pinfunction "1_1") (pintype "passive"))
    )
    (net (code "131") (name "Net-(U1-CII)") (class "Default")
      (node (ref "C3") (pin "2") (pinfunction "2_2") (pintype "passive"))
      (node (ref "R2") (pin "2") (pinfunction "2_2") (pintype "passive"))
      (node (ref "R3") (pin "2") (pinfunction "2_2") (pintype "passive"))
      (node (ref "U1") (pin "5") (pinfunction "CII_5") (pintype "output"))
    )
    (net (code "132") (name "Net-(U1-DRC)") (class "Default")
      (node (ref "R5") (pin "2") (pinfunction "2_2") (pintype "passive"))
      (node (ref "U1") (pin "8") (pinfunction "DRC_8") (pintype "passive"))
    )
    (net (code "133") (name "Net-(U1-IPX)") (class "Default")
      (node (ref "L1") (pin "2") (pintype "passive"))
      (node (ref "R1") (pin "1") (pinfunction "1_1") (pintype "passive"))
      (node (ref "R5") (pin "1") (pinfunction "1_1") (pintype "passive"))
      (node (ref "U1") (pin "1") (pinfunction "SWC_1") (pintype "passive"))
      (node (ref "U1") (pin "7") (pinfunction "IPX_7") (pintype "passive"))
    )
    (net (code "134") (name "Net-(U1-TC)") (class "Default")
      (node (ref "C2") (pin "2") (pinfunction "2_2") (pintype "passive"))
      (node (ref "U1") (pin "3") (pinfunction "TC_3") (pintype "passive"))
    )
    (net (code "135") (name "Net-(U5-VOUT)") (class "Default")
      (node (ref "C9") (pin "2") (pinfunction "2_2") (pintype "passive"))
      (node (ref "U5") (pin "14") (pinfunction "VOUT_14") (pintype "passive"))
    )
    (net (code "136") (name "VCC") (class "Default")
      (node (ref "B") (pin "1") (pinfunction "A_1") (pintype "passive"))
      (node (ref "C10") (pin "2") (pinfunction "2_2") (pintype "passive"))
      (node (ref "C11") (pin "1") (pinfunction "1_1") (pintype "passive"))
      (node (ref "C12") (pin "1") (pinfunction "1_1") (pintype "passive"))
      (node (ref "C5") (pin "1") (pinfunction "1_1") (pintype "passive"))
      (node (ref "C8") (pin "2") (pinfunction "2_2") (pintype "passive"))
      (node (ref "JP1") (pin "1") (pinfunction "1_1") (pintype "passive"))
      (node (ref "U2") (pin "2") (pinfunction "OUT_2") (pintype "power_in"))
      (node (ref "U3") (pin "3") (pinfunction "VIN_3") (pintype "passive"))
      (node (ref "U4") (pin "31") (pinfunction "~{B}L_31") (pintype "passive"))
      (node (ref "U4") (pin "32") (pinfunction "VDD_32") (pintype "passive"))
      (node (ref "U4") (pin "33") (pinfunction "DIR_33") (pintype "passive"))
      (node (ref "U5") (pin "16") (pinfunction "VCC_16") (pintype "passive"))
      (node (ref "U6") (pin "12") (pinfunction "VDD_12") (pintype "passive"))
      (node (ref "U8") (pin "14") (pinfunction "VCC_14") (pintype "passive"))
    )
    (net (code "137") (name "VCC3") (class "Default")
      (node (ref "C7") (pin "2") (pinfunction "2_2") (pintype "passive"))
      (node (ref "U3") (pin "2") (pinfunction "VOUT_2") (pintype "passive"))
      (node (ref "U7") (pin "2") (pinfunction "VCC_2") (pintype "passive"))
    )
    (net (code "138") (name "VCC12") (class "Default")
      (node (ref "C1") (pin "2") (pinfunction "2_2") (pintype "passive"))
      (node (ref "C13") (pin "1") (pinfunction "1_1") (pintype "passive"))
      (node (ref "C6") (pin "2") (pinfunction "2_2") (pintype "passive"))
      (node (ref "D3") (pin "1") (pinfunction "K_1") (pintype "passive"))
      (node (ref "F1") (pin "2") (pinfunction "2_2") (pintype "passive"))
      (node (ref "LED1") (pin "0") (pinfunction "B+_0") (pintype "passive"))
      (node (ref "LED1") (pin "1") (pinfunction "G+_1") (pintype "passive"))
      (node (ref "LED1") (pin "2") (pinfunction "R+_2") (pintype "passive"))
      (node (ref "LED6") (pin "0") (pinfunction "B+_0") (pintype "passive"))
      (node (ref "LED6") (pin "1") (pinfunction "G+_1") (pintype "passive"))
      (node (ref "LED6") (pin "2") (pinfunction "R+_2") (pintype "passive"))
      (node (ref "R1") (pin "2") (pinfunction "2_2") (pintype "passive"))
      (node (ref "U1") (pin "6") (pinfunction "VCC_6") (pintype "power_in"))
      (node (ref "U2") (pin "1") (pinfunction "IN_1") (pintype "power_in"))
    )
    (net (code "139") (name "VH") (class "Default")
      (node (ref "C4") (pin "1") (pinfunction "1_1") (pintype "passive"))
      (node (ref "D1") (pin "1") (pinfunction "K_1") (pintype "passive"))
      (node (ref "R10") (pin "2") (pinfunction "2_2") (pintype "passive"))
      (node (ref "R11") (pin "2") (pinfunction "2_2") (pintype "passive"))
      (node (ref "R12") (pin "2") (pinfunction "2_2") (pintype "passive"))
      (node (ref "R13") (pin "1") (pinfunction "1_1") (pintype "passive"))
      (node (ref "R14") (pin "1") (pinfunction "1_1") (pintype "passive"))
      (node (ref "R15") (pin "1") (pinfunction "1_1") (pintype "passive"))
      (node (ref "R16") (pin "1") (pinfunction "1_1") (pintype "passive"))
      (node (ref "R2") (pin "1") (pinfunction "1_1") (pintype "passive"))
      (node (ref "R6") (pin "2") (pinfunction "2_2") (pintype "passive"))
      (node (ref "R7") (pin "2") (pinfunction "2_2") (pintype "passive"))
      (node (ref "R8") (pin "2") (pinfunction "2_2") (pintype "passive"))
      (node (ref "R9") (pin "2") (pinfunction "2_2") (pintype "passive"))
    )
    (net (code "140") (name "unconnected-(PWR-N-Pad3)") (class "Default")
      (node (ref "PWR") (pin "3") (pinfunction "N_3") (pintype "passive"))
    )
    (net (code "141") (name "unconnected-(U4-Dout1{slash}Din4(B)-Pad39)") (class "Default")
      (node (ref "U4") (pin "39") (pinfunction "Dout1/Din4(B)_39") (pintype "passive"))
    )
    (net (code "142") (name "unconnected-(U4-Dout2{slash}Din3(B)-Pad38)") (class "Default")
      (node (ref "U4") (pin "38") (pinfunction "Dout2/Din3(B)_38") (pintype "passive"))
    )
    (net (code "143") (name "unconnected-(U4-Dout3{slash}Din2(B)-Pad37)") (class "Default")
      (node (ref "U4") (pin "37") (pinfunction "Dout3/Din2(B)_37") (pintype "passive"))
    )
    (net (code "144") (name "unconnected-(U4-Dout4{slash}Din1(B)-Pad36)") (class "Default")
      (node (ref "U4") (pin "36") (pinfunction "Dout4/Din1(B)_36") (pintype "passive"))
    )
    (net (code "145") (name "unconnected-(U4-HVout1{slash}64-Pad24)") (class "Default")
      (node (ref "U4") (pin "24") (pinfunction "HVout1/64_24") (pintype "passive"))
    )
    (net (code "146") (name "unconnected-(U4-HVout2{slash}63-Pad23)") (class "Default")
      (node (ref "U4") (pin "23") (pinfunction "HVout2/63_23") (pintype "passive"))
    )
    (net (code "147") (name "unconnected-(U4-HVout3{slash}62-Pad22)") (class "Default")
      (node (ref "U4") (pin "22") (pinfunction "HVout3/62_22") (pintype "passive"))
    )
    (net (code "148") (name "unconnected-(U4-HVout4{slash}61-Pad21)") (class "Default")
      (node (ref "U4") (pin "21") (pinfunction "HVout4/61_21") (pintype "passive"))
    )
    (net (code "149") (name "unconnected-(U5-CMODE-Pad13)") (class "Default")
      (node (ref "U5") (pin "13") (pinfunction "CMODE_13") (pintype "passive"))
    )
    (net (code "150") (name "unconnected-(U5-DCLKO-Pad12)") (class "Default")
      (node (ref "U5") (pin "12") (pinfunction "DCLKO_12") (pintype "passive"))
    )
    (net (code "151") (name "unconnected-(U5-DOUT-Pad15)") (class "Default")
      (node (ref "U5") (pin "15") (pinfunction "DOUT_15") (pintype "passive"))
    )
    (net (code "152") (name "unconnected-(U5-GMODE-Pad2)") (class "Default")
      (node (ref "U5") (pin "2") (pinfunction "GMODE_2") (pintype "passive"))
    )
    (net (code "153") (name "unconnected-(U5-OMODE-Pad3)") (class "Default")
      (node (ref "U5") (pin "3") (pinfunction "OMODE_3") (pintype "passive"))
    )
    (net (code "154") (name "unconnected-(U6-NULL-Pad13)") (class "Default")
      (node (ref "U6") (pin "13") (pinfunction "NULL_13") (pintype "passive"))
    )
    (net (code "155") (name "unconnected-(U6-NULL-Pad14)") (class "Default")
      (node (ref "U6") (pin "14") (pinfunction "NULL_14") (pintype "passive"))
    )
    (net (code "156") (name "unconnected-(U6-TEST-Pad2)") (class "Default")
      (node (ref "U6") (pin "2") (pinfunction "TEST_2") (pintype "passive"))
    )
    (net (code "157") (name "unconnected-(U6-VOUT-Pad15)") (class "Default")
      (node (ref "U6") (pin "15") (pinfunction "VOUT_15") (pintype "passive"))
    )
    (net (code "158") (name "unconnected-(U7-ADC1-Pad18)") (class "Default")
      (node (ref "U7") (pin "18") (pinfunction "ADC1_18") (pintype "passive"))
    )
    (net (code "159") (name "unconnected-(U7-IO5-Pad7)") (class "Default")
      (node (ref "U7") (pin "7") (pinfunction "IO5_7") (pintype "passive"))
    )
    (net (code "160") (name "unconnected-(U7-IO6-Pad4)") (class "Default")
      (node (ref "U7") (pin "4") (pinfunction "IO6_4") (pintype "passive"))
    )
    (net (code "161") (name "unconnected-(U7-IO7-Pad3)") (class "Default")
      (node (ref "U7") (pin "3") (pinfunction "IO7_3") (pintype "passive"))
    )
    (net (code "162") (name "unconnected-(U7-PWM1-Pad11)") (class "Default")
      (node (ref "U7") (pin "11") (pinfunction "PWM1_11") (pintype "passive"))
    )
    (net (code "163") (name "unconnected-(U7-PWM3-Pad12)") (class "Default")
      (node (ref "U7") (pin "12") (pinfunction "PWM3_12") (pintype "passive"))
    )
    (net (code "164") (name "unconnected-(U7-PWM4-Pad13)") (class "Default")
      (node (ref "U7") (pin "13") (pinfunction "PWM4_13") (pintype "passive"))
    )
    (net (code "165") (name "unconnected-(U7-RES-Pad5)") (class "Default")
      (node (ref "U7") (pin "5") (pinfunction "RES_5") (pintype "passive"))
    )
    (net (code "166") (name "unconnected-(U7-REST-Pad10)") (class "Default")
      (node (ref "U7") (pin "10") (pinfunction "REST_10") (pintype "passive"))
    )
    (net (code "167") (name "unconnected-(U7-U+-Pad8)") (class "Default")
      (node (ref "U7") (pin "8") (pinfunction "U+_8") (pintype "passive"))
    )
    (net (code "168") (name "unconnected-(U7-U--Pad9)") (class "Default")
      (node (ref "U7") (pin "9") (pinfunction "U-_9") (pintype "passive"))
    )
    (net (code "169") (name "unconnected-(U8-P0.0{slash}AD0-Pad40)") (class "Default")
      (node (ref "U8") (pin "40") (pinfunction "P0.0/AD0_40") (pintype "passive"))
    )
    (net (code "170") (name "unconnected-(U8-P0.1{slash}AD1-Pad41)") (class "Default")
      (node (ref "U8") (pin "41") (pinfunction "P0.1/AD1_41") (pintype "passive"))
    )
    (net (code "171") (name "unconnected-(U8-P0.2{slash}AD2-Pad42)") (class "Default")
      (node (ref "U8") (pin "42") (pinfunction "P0.2/AD2_42") (pintype "passive"))
    )
    (net (code "172") (name "unconnected-(U8-P0.3{slash}AD3-Pad43)") (class "Default")
      (node (ref "U8") (pin "43") (pinfunction "P0.3/AD3_43") (pintype "passive"))
    )
    (net (code "173") (name "unconnected-(U8-P0.4{slash}AD4-Pad44)") (class "Default")
      (node (ref "U8") (pin "44") (pinfunction "P0.4/AD4_44") (pintype "passive"))
    )
    (net (code "174") (name "unconnected-(U8-P0.5{slash}AD5-Pad1)") (class "Default")
      (node (ref "U8") (pin "1") (pinfunction "P0.5/AD5_1") (pintype "passive"))
    )
    (net (code "175") (name "unconnected-(U8-P0.6{slash}AD6-Pad2)") (class "Default")
      (node (ref "U8") (pin "2") (pinfunction "P0.6/AD6_2") (pintype "passive"))
    )
    (net (code "176") (name "unconnected-(U8-P0.7{slash}AD7-Pad3)") (class "Default")
      (node (ref "U8") (pin "3") (pinfunction "P0.7/AD7_3") (pintype "passive"))
    )
    (net (code "177") (name "unconnected-(U8-P1.7{slash}ADC7{slash}TXD_3{slash}XTAL1-Pad12)") (class "Default")
      (node (ref "U8") (pin "12") (pinfunction "P1.7/ADC7/TXD_3/XTAL1_12") (pintype "passive"))
    )
    (net (code "178") (name "unconnected-(U8-P2.6{slash}A14{slash}CCP1_3-Pad36)") (class "Default")
      (node (ref "U8") (pin "36") (pinfunction "P2.6/A14/CCP1_3_36") (pintype "passive"))
    )
    (net (code "179") (name "unconnected-(U8-P2.7{slash}A15{slash}CCP2_3-Pad37)") (class "Default")
      (node (ref "U8") (pin "37") (pinfunction "P2.7/A15/CCP2_3_37") (pintype "passive"))
    )
    (net (code "180") (name "unconnected-(U8-P3.4{slash}T0{slash}T1CLKO{slash}ECI_2-Pad22)") (class "Default")
      (node (ref "U8") (pin "22") (pinfunction "P3.4/T0/T1CLKO/ECI_2_22") (pintype "passive"))
    )
    (net (code "181") (name "unconnected-(U8-P3.5{slash}T1{slash}T0CLKO{slash}CCP0_2-Pad23)") (class "Default")
      (node (ref "U8") (pin "23") (pinfunction "P3.5/T1/T0CLKO/CCP0_2_23") (pintype "passive"))
    )
    (net (code "182") (name "unconnected-(U8-P4.5{slash}ALE-Pad38)") (class "Default")
      (node (ref "U8") (pin "38") (pinfunction "P4.5/ALE_38") (pintype "passive"))
    )
    (net (code "183") (name "unconnected-(U8-P4.6{slash}RXD2_2-Pad39)") (class "Default")
      (node (ref "U8") (pin "39") (pinfunction "P4.6/RXD2_2_39") (pintype "passive"))
    )
    (net (code "184") (name "unconnected-(U8-P4.7{slash}TXD2_2-Pad6)") (class "Default")
      (node (ref "U8") (pin "6") (pinfunction "P4.7/TXD2_2_6") (pintype "passive"))
    )
    (net (code "185") (name "unconnected-(U8-P5.4{slash}RST{slash}MCLKO{slash}SS_3-Pad13)") (class "Default")
      (node (ref "U8") (pin "13") (pinfunction "P5.4/RST/MCLKO/SS_3_13") (pintype "passive"))
    )
    (net (code "186") (name "unconnected-(U8-P5.5-Pad15)") (class "Default")
      (node (ref "U8") (pin "15") (pinfunction "P5.5_15") (pintype "passive"))
    )
  )
)
